# CAN.net
KiCad netlist of a schematic drawn in Altium Designer
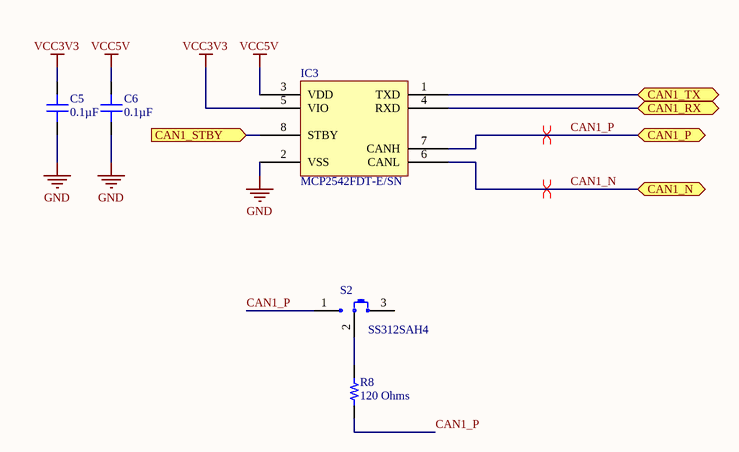
[diagram p0: CAN.SchDoc]

(export (version "E")
  (design (tool "Eeschema 10.0.6"))
  (components
    (comp (ref "C5")
      (value "0.1µF")
      (footprint "CAP 0201_0603")
      (description "CAP CER 0.1UF 16V X5R 0201")
      (fields (field (name "PART NUMBER") "EMK063BJ104KP-F") (field (name "MANUFACTURER") "Taiyo Yuden"))
      (libsource (lib "Celestial") (part "Capacitor"))
    )
    (comp (ref "C6")
      (value "0.1µF")
      (footprint "CAP 0201_0603")
      (description "CAP CER 0.1UF 16V X5R 0201")
      (fields (field (name "PART NUMBER") "EMK063BJ104KP-F") (field (name "MANUFACTURER") "Taiyo Yuden"))
      (libsource (lib "Celestial") (part "Capacitor"))
    )
    (comp (ref "IC3")
      (value "MCP2542FDT-E/SN")
      (footprint "MICROCHIP SOIC-8 150MIL WIDE")
      (description "IC TRANSCEIVER 1/1 8SOIC")
      (fields (field (name "MANUFACTURER") "Microchip Technology"))
      (libsource (lib "Celestial") (part "MICROCHIP MCP2542FD"))
    )
    (comp (ref "R8")
      (value "120 Ohms")
      (footprint "RES 0402_1005")
      (description "RES SMD 120 OHM 5% 1/16W 0402")
      (fields (field (name "PART NUMBER") "RC0402JR-07120RL") (field (name "MANUFACTURER") "Yageo"))
      (libsource (lib "CAL") (part "Resistor"))
    )
    (comp (ref "S2")
      (value "SS312SAH4")
      (footprint "NKK SS312SAH4")
      (description "SWITCH SLIDE SPDT 0.4VA 28V")
      (fields (field (name "MANUFACTURER") "NKK Switches"))
      (libsource (lib "CAL") (part "NKK SS312"))
    )
  )
  (nets
    (net (code "1") (name "/CAN1_N") (class "Default")
      (node (ref "IC3") (pin "6") (pinfunction "CANL_6") (pintype "passive"))
    )
    (net (code "2") (name "/CAN1_P") (class "Default")
      (node (ref "IC3") (pin "7") (pinfunction "CANH_7") (pintype "passive"))
      (node (ref "R8") (pin "1") (pinfunction "1_1") (pintype "passive"))
      (node (ref "S2") (pin "1") (pinfunction "1_1") (pintype "passive"))
    )
    (net (code "3") (name "/CAN1_RX") (class "Default")
      (node (ref "IC3") (pin "4") (pinfunction "RXD_4") (pintype "passive"))
    )
    (net (code "4") (name "/CAN1_STBY") (class "Default")
      (node (ref "IC3") (pin "8") (pinfunction "STBY_8") (pintype "passive"))
    )
    (net (code "5") (name "/CAN1_TX") (class "Default")
      (node (ref "IC3") (pin "1") (pinfunction "TXD_1") (pintype "passive"))
    )
    (net (code "6") (name "GND") (class "Default")
      (node (ref "C5") (pin "1") (pinfunction "1_1") (pintype "passive"))
      (node (ref "C6") (pin "1") (pinfunction "1_1") (pintype "passive"))
      (node (ref "IC3") (pin "2") (pinfunction "VSS_2") (pintype "passive"))
    )
    (net (code "7") (name "Net-(S2-COM)") (class "Default")
      (node (ref "R8") (pin "2") (pinfunction "2_2") (pintype "passive"))
      (node (ref "S2") (pin "2") (pinfunction "COM_2") (pintype "passive"))
    )
    (net (code "8") (name "VCC3V3") (class "Default")
      (node (ref "C5") (pin "2") (pinfunction "2_2") (pintype "passive"))
      (node (ref "IC3") (pin "5") (pinfunction "VIO_5") (pintype "passive"))
    )
    (net (code "9") (name "VCC5V") (class "Default")
      (node (ref "C6") (pin "2") (pinfunction "2_2") (pintype "passive"))
      (node (ref "IC3") (pin "3") (pinfunction "VDD_3") (pintype "passive"))
    )
    (net (code "10") (name "unconnected-(S2-Pad3)") (class "Default")
      (node (ref "S2") (pin "3") (pinfunction "3_3") (pintype "passive"))
    )
  )
)
